# licznik.net
KiCad netlist of a schematic drawn in EAGLE
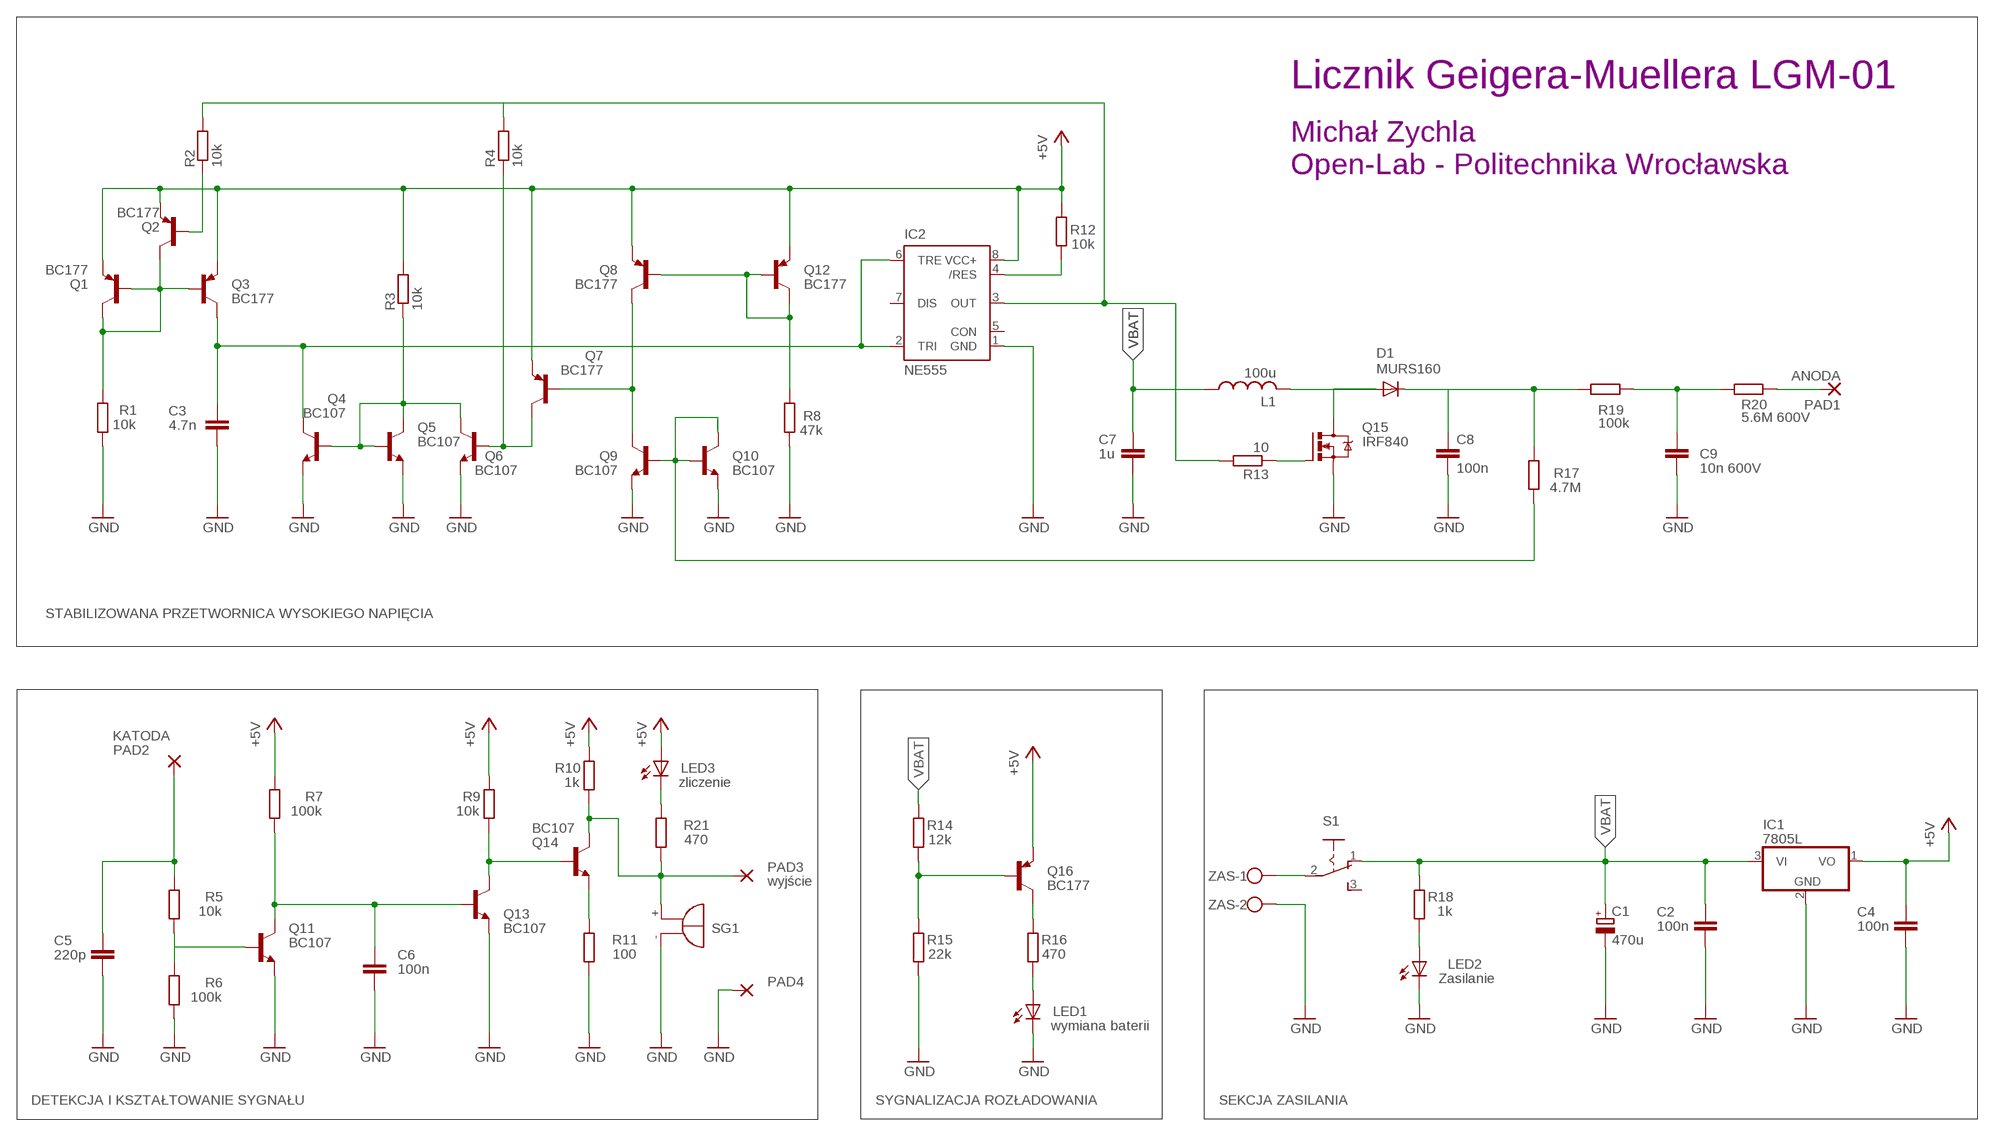
[diagram p0: schematic, sheet 1]

(export (version "E")
  (design (tool "Eeschema 10.0.6"))
  (components
    (comp (ref "C1")
      (value "470u")
      (footprint "eagle-import:E3,5-8")
      (libsource (lib "eagle-import") (part "CPOL-EUE3.5-8"))
    )
    (comp (ref "C2")
      (value "100n")
      (footprint "eagle-import:C5B3")
      (libsource (lib "eagle-import") (part "C5/3"))
    )
    (comp (ref "C3")
      (value "4.7n")
      (footprint "eagle-import:C5B3")
      (libsource (lib "eagle-import") (part "C5/3"))
    )
    (comp (ref "C4")
      (value "100n")
      (footprint "eagle-import:C5B3")
      (libsource (lib "eagle-import") (part "C5/3"))
    )
    (comp (ref "C5")
      (value "220p")
      (footprint "eagle-import:C5B3")
      (libsource (lib "eagle-import") (part "C5/3"))
    )
    (comp (ref "C6")
      (value "100n")
      (footprint "eagle-import:C5B3")
      (libsource (lib "eagle-import") (part "C5/3"))
    )
    (comp (ref "C7")
      (value "1u")
      (footprint "eagle-import:C5B3")
      (libsource (lib "eagle-import") (part "C5/3"))
    )
    (comp (ref "C8")
      (value "100n")
      (footprint "eagle-import:C075-032X103")
      (libsource (lib "eagle-import") (part "C-EU075-032X103"))
    )
    (comp (ref "C9")
      (value "10n 600V")
      (footprint "eagle-import:C5B3")
      (libsource (lib "eagle-import") (part "C5/3"))
    )
    (comp (ref "D1")
      (value "MURS160")
      (footprint "eagle-import:SMB")
      (libsource (lib "eagle-import") (part "DIODE-SMB"))
    )
    (comp (ref "IC1")
      (value "7805L")
      (footprint "eagle-import:TO92")
      (libsource (lib "eagle-import") (part "78L05"))
    )
    (comp (ref "IC2")
      (value "NE555")
      (footprint "eagle-import:DIL-08")
      (fields (field (name "MF") "Arrow Electronics") (field (name "MPN") "NE555N"))
      (libsource (lib "eagle-import") (part "NE555"))
    )
    (comp (ref "L1")
      (value "100u")
      (footprint "eagle-import:TJ3-U1")
      (libsource (lib "eagle-import") (part "L-USTJ3-U1"))
    )
    (comp (ref "LED1")
      (value "wymiana baterii")
      (footprint "eagle-import:LED3MM")
      (libsource (lib "eagle-import") (part "LED3MM"))
    )
    (comp (ref "LED2")
      (value "Zasilanie")
      (footprint "eagle-import:LED3MM")
      (libsource (lib "eagle-import") (part "LED3MM"))
    )
    (comp (ref "LED3")
      (value "zliczenie")
      (footprint "eagle-import:LED3MM")
      (libsource (lib "eagle-import") (part "LED3MM"))
    )
    (comp (ref "PAD1")
      (value "ANODA")
      (footprint "eagle-import:2,15_1,0")
      (libsource (lib "eagle-import") (part "WIREPAD2,15/1,0"))
    )
    (comp (ref "PAD2")
      (value "KATODA")
      (footprint "eagle-import:2,15_1,0")
      (libsource (lib "eagle-import") (part "WIREPAD2,15/1,0"))
    )
    (comp (ref "PAD3")
      (value "wyjście")
      (footprint "eagle-import:2,15_1,0")
      (libsource (lib "eagle-import") (part "WIREPAD2,15/1,0"))
    )
    (comp (ref "PAD4")
      (value "WIREPAD2,15/1,0")
      (footprint "eagle-import:2,15_1,0")
      (libsource (lib "eagle-import") (part "WIREPAD2,15/1,0"))
    )
    (comp (ref "Q1")
      (value "BC177")
      (footprint "eagle-import:TO18")
      (libsource (lib "eagle-import") (part "BC177"))
    )
    (comp (ref "Q2")
      (value "BC177")
      (footprint "eagle-import:TO18")
      (libsource (lib "eagle-import") (part "BC177"))
    )
    (comp (ref "Q3")
      (value "BC177")
      (footprint "eagle-import:TO18")
      (libsource (lib "eagle-import") (part "BC177"))
    )
    (comp (ref "Q4")
      (value "BC107")
      (footprint "eagle-import:TO18")
      (libsource (lib "eagle-import") (part "BC107"))
    )
    (comp (ref "Q5")
      (value "BC107")
      (footprint "eagle-import:TO18")
      (libsource (lib "eagle-import") (part "BC107"))
    )
    (comp (ref "Q6")
      (value "BC107")
      (footprint "eagle-import:TO18")
      (libsource (lib "eagle-import") (part "BC107"))
    )
    (comp (ref "Q7")
      (value "BC177")
      (footprint "eagle-import:TO18")
      (libsource (lib "eagle-import") (part "BC177"))
    )
    (comp (ref "Q8")
      (value "BC177")
      (footprint "eagle-import:TO18")
      (libsource (lib "eagle-import") (part "BC177"))
    )
    (comp (ref "Q9")
      (value "BC107")
      (footprint "eagle-import:TO18")
      (libsource (lib "eagle-import") (part "BC107"))
    )
    (comp (ref "Q10")
      (value "BC107")
      (footprint "eagle-import:TO18")
      (libsource (lib "eagle-import") (part "BC107"))
    )
    (comp (ref "Q11")
      (value "BC107")
      (footprint "eagle-import:TO18")
      (libsource (lib "eagle-import") (part "BC107"))
    )
    (comp (ref "Q12")
      (value "BC177")
      (footprint "eagle-import:TO18")
      (libsource (lib "eagle-import") (part "BC177"))
    )
    (comp (ref "Q13")
      (value "BC107")
      (footprint "eagle-import:TO18")
      (libsource (lib "eagle-import") (part "BC107"))
    )
    (comp (ref "Q14")
      (value "BC107")
      (footprint "eagle-import:TO18")
      (libsource (lib "eagle-import") (part "BC107"))
    )
    (comp (ref "Q15")
      (value "IRF840")
      (footprint "eagle-import:TO220BV")
      (libsource (lib "eagle-import") (part "IRF740"))
    )
    (comp (ref "Q16")
      (value "BC177")
      (footprint "eagle-import:TO18")
      (libsource (lib "eagle-import") (part "BC177"))
    )
    (comp (ref "R1")
      (value "10k")
      (footprint "eagle-import:0207_10")
      (libsource (lib "eagle-import") (part "R-EU_0207/10"))
    )
    (comp (ref "R2")
      (value "10k")
      (footprint "eagle-import:0207_10")
      (libsource (lib "eagle-import") (part "R-EU_0207/10"))
    )
    (comp (ref "R3")
      (value "10k")
      (footprint "eagle-import:0207_10")
      (libsource (lib "eagle-import") (part "R-EU_0207/10"))
    )
    (comp (ref "R4")
      (value "10k")
      (footprint "eagle-import:0207_10")
      (libsource (lib "eagle-import") (part "R-EU_0207/10"))
    )
    (comp (ref "R5")
      (value "10k")
      (footprint "eagle-import:0207_10")
      (libsource (lib "eagle-import") (part "R-EU_0207/10"))
    )
    (comp (ref "R6")
      (value "100k")
      (footprint "eagle-import:0207_10")
      (libsource (lib "eagle-import") (part "R-EU_0207/10"))
    )
    (comp (ref "R7")
      (value "100k")
      (footprint "eagle-import:0207_10")
      (libsource (lib "eagle-import") (part "R-EU_0207/10"))
    )
    (comp (ref "R8")
      (value "47k")
      (footprint "eagle-import:0207_10")
      (libsource (lib "eagle-import") (part "R-EU_0207/10"))
    )
    (comp (ref "R9")
      (value "10k")
      (footprint "eagle-import:0207_10")
      (libsource (lib "eagle-import") (part "R-EU_0207/10"))
    )
    (comp (ref "R10")
      (value "1k")
      (footprint "eagle-import:0207_10")
      (libsource (lib "eagle-import") (part "R-EU_0207/10"))
    )
    (comp (ref "R11")
      (value "100")
      (footprint "eagle-import:0207_10")
      (libsource (lib "eagle-import") (part "R-EU_0207/10"))
    )
    (comp (ref "R12")
      (value "10k")
      (footprint "eagle-import:0207_10")
      (libsource (lib "eagle-import") (part "R-EU_0207/10"))
    )
    (comp (ref "R13")
      (value "10")
      (footprint "eagle-import:0207_10")
      (libsource (lib "eagle-import") (part "R-EU_0207/10"))
    )
    (comp (ref "R14")
      (value "12k")
      (footprint "eagle-import:0207_10")
      (libsource (lib "eagle-import") (part "R-EU_0207/10"))
    )
    (comp (ref "R15")
      (value "22k")
      (footprint "eagle-import:0207_10")
      (libsource (lib "eagle-import") (part "R-EU_0207/10"))
    )
    (comp (ref "R16")
      (value "470")
      (footprint "eagle-import:0207_10")
      (libsource (lib "eagle-import") (part "R-EU_0207/10"))
    )
    (comp (ref "R17")
      (value "4.7M")
      (footprint "eagle-import:0207_10")
      (libsource (lib "eagle-import") (part "R-EU_0207/10"))
    )
    (comp (ref "R18")
      (value "1k")
      (footprint "eagle-import:0207_10")
      (libsource (lib "eagle-import") (part "R-EU_0207/10"))
    )
    (comp (ref "R19")
      (value "100k")
      (footprint "eagle-import:0207_10")
      (libsource (lib "eagle-import") (part "R-EU_0207/10"))
    )
    (comp (ref "R20")
      (value "5.6M 600V")
      (footprint "eagle-import:0411_12")
      (libsource (lib "eagle-import") (part "R-EU_0411/12"))
    )
    (comp (ref "R21")
      (value "470")
      (footprint "eagle-import:0207_10")
      (libsource (lib "eagle-import") (part "R-EU_0207/10"))
    )
    (comp (ref "S1")
      (value "255SB")
      (footprint "eagle-import:255SB")
      (libsource (lib "eagle-import") (part "255SB"))
    )
    (comp (ref "SG1")
      (value "F/QMBIII")
      (footprint "eagle-import:F_QMBIII")
      (libsource (lib "eagle-import") (part "F/QMBIII"))
    )
    (comp (ref "ZAS")
      (value "W237-102")
      (footprint "eagle-import:W237-102")
      (fields (field (name "MPN") "237-102"))
      (libsource (lib "eagle-import") (part "W237-102"))
    )
  )
  (nets
    (net (code "1") (name "+5V") (class "Default")
      (node (ref "C4") (pin "1") (pinfunction "1_1") (pintype "passive"))
      (node (ref "IC1") (pin "1") (pinfunction "VO_1") (pintype "passive"))
      (node (ref "IC2") (pin "8") (pinfunction "VCC+_8") (pintype "power_in"))
      (node (ref "LED3") (pin "A") (pinfunction "A_A") (pintype "passive"))
      (node (ref "Q1") (pin "1") (pinfunction "E_1") (pintype "passive"))
      (node (ref "Q12") (pin "1") (pinfunction "E_1") (pintype "passive"))
      (node (ref "Q16") (pin "1") (pinfunction "E_1") (pintype "passive"))
      (node (ref "Q2") (pin "1") (pinfunction "E_1") (pintype "passive"))
      (node (ref "Q3") (pin "1") (pinfunction "E_1") (pintype "passive"))
      (node (ref "Q7") (pin "1") (pinfunction "E_1") (pintype "passive"))
      (node (ref "Q8") (pin "1") (pinfunction "E_1") (pintype "passive"))
      (node (ref "R10") (pin "2") (pinfunction "2_2") (pintype "passive"))
      (node (ref "R12") (pin "2") (pinfunction "2_2") (pintype "passive"))
      (node (ref "R3") (pin "2") (pinfunction "2_2") (pintype "passive"))
      (node (ref "R7") (pin "2") (pinfunction "2_2") (pintype "passive"))
      (node (ref "R9") (pin "2") (pinfunction "2_2") (pintype "passive"))
    )
    (net (code "2") (name "GND") (class "Default")
      (node (ref "C1") (pin "-") (pinfunction "-_-") (pintype "passive"))
      (node (ref "C2") (pin "2") (pinfunction "2_2") (pintype "passive"))
      (node (ref "C3") (pin "2") (pinfunction "2_2") (pintype "passive"))
      (node (ref "C4") (pin "2") (pinfunction "2_2") (pintype "passive"))
      (node (ref "C5") (pin "2") (pinfunction "2_2") (pintype "passive"))
      (node (ref "C6") (pin "2") (pinfunction "2_2") (pintype "passive"))
      (node (ref "C7") (pin "2") (pinfunction "2_2") (pintype "passive"))
      (node (ref "C8") (pin "2") (pinfunction "2_2") (pintype "passive"))
      (node (ref "C9") (pin "2") (pinfunction "2_2") (pintype "passive"))
      (node (ref "IC1") (pin "2") (pinfunction "GND_2") (pintype "passive"))
      (node (ref "IC2") (pin "1") (pinfunction "GND_1") (pintype "power_in"))
      (node (ref "LED1") (pin "K") (pinfunction "C_K") (pintype "passive"))
      (node (ref "LED2") (pin "K") (pinfunction "C_K") (pintype "passive"))
      (node (ref "PAD4") (pin "1") (pinfunction "P_1") (pintype "passive"))
      (node (ref "Q10") (pin "1") (pinfunction "E_1") (pintype "passive"))
      (node (ref "Q11") (pin "1") (pinfunction "E_1") (pintype "passive"))
      (node (ref "Q13") (pin "1") (pinfunction "E_1") (pintype "passive"))
      (node (ref "Q15") (pin "S") (pinfunction "S_S") (pintype "passive"))
      (node (ref "Q4") (pin "1") (pinfunction "E_1") (pintype "passive"))
      (node (ref "Q5") (pin "1") (pinfunction "E_1") (pintype "passive"))
      (node (ref "Q6") (pin "1") (pinfunction "E_1") (pintype "passive"))
      (node (ref "Q9") (pin "1") (pinfunction "E_1") (pintype "passive"))
      (node (ref "R1") (pin "1") (pinfunction "1_1") (pintype "passive"))
      (node (ref "R11") (pin "1") (pinfunction "1_1") (pintype "passive"))
      (node (ref "R15") (pin "1") (pinfunction "1_1") (pintype "passive"))
      (node (ref "R6") (pin "1") (pinfunction "1_1") (pintype "passive"))
      (node (ref "R8") (pin "1") (pinfunction "1_1") (pintype "passive"))
      (node (ref "SG1") (pin "-") (pinfunction "+_-") (pintype "passive"))
      (node (ref "ZAS") (pin "2") (pinfunction "KL_2") (pintype "passive"))
    )
    (net (code "3") (name "Net-(C8-Pad1)") (class "Default")
      (node (ref "C8") (pin "1") (pinfunction "1_1") (pintype "passive"))
      (node (ref "D1") (pin "C") (pinfunction "C_C") (pintype "passive"))
      (node (ref "R17") (pin "2") (pinfunction "2_2") (pintype "passive"))
      (node (ref "R19") (pin "2") (pinfunction "2_2") (pintype "passive"))
    )
    (net (code "4") (name "Net-(C9-Pad1)") (class "Default")
      (node (ref "C9") (pin "1") (pinfunction "1_1") (pintype "passive"))
      (node (ref "R19") (pin "1") (pinfunction "1_1") (pintype "passive"))
      (node (ref "R20") (pin "1") (pinfunction "1_1") (pintype "passive"))
    )
    (net (code "5") (name "Net-(D1-PadA)") (class "Default")
      (node (ref "D1") (pin "A") (pinfunction "A_A") (pintype "passive"))
      (node (ref "L1") (pin "2") (pinfunction "2_2") (pintype "passive"))
      (node (ref "Q15") (pin "D") (pinfunction "D_D") (pintype "passive"))
    )
    (net (code "6") (name "Net-(IC2-OUT)") (class "Default")
      (node (ref "IC2") (pin "3") (pinfunction "OUT_3") (pintype "output"))
      (node (ref "R13") (pin "2") (pinfunction "2_2") (pintype "passive"))
      (node (ref "R2") (pin "2") (pinfunction "2_2") (pintype "passive"))
      (node (ref "R4") (pin "2") (pinfunction "2_2") (pintype "passive"))
    )
    (net (code "7") (name "Net-(IC2-TRE)") (class "Default")
      (node (ref "C3") (pin "1") (pinfunction "1_1") (pintype "passive"))
      (node (ref "IC2") (pin "2") (pinfunction "TRI_2") (pintype "input"))
      (node (ref "IC2") (pin "6") (pinfunction "TRE_6") (pintype "input"))
      (node (ref "Q3") (pin "3") (pinfunction "C_3") (pintype "passive"))
      (node (ref "Q4") (pin "3") (pinfunction "C_3") (pintype "passive"))
    )
    (net (code "8") (name "Net-(IC2-{slash}RES)") (class "Default")
      (node (ref "IC2") (pin "4") (pinfunction "/RES_4") (pintype "input"))
      (node (ref "R12") (pin "1") (pinfunction "1_1") (pintype "passive"))
    )
    (net (code "9") (name "Net-(LED1-PadA)") (class "Default")
      (node (ref "LED1") (pin "A") (pinfunction "A_A") (pintype "passive"))
      (node (ref "R16") (pin "1") (pinfunction "1_1") (pintype "passive"))
    )
    (net (code "10") (name "Net-(LED2-PadA)") (class "Default")
      (node (ref "LED2") (pin "A") (pinfunction "A_A") (pintype "passive"))
      (node (ref "R18") (pin "1") (pinfunction "1_1") (pintype "passive"))
    )
    (net (code "11") (name "Net-(LED3-C)") (class "Default")
      (node (ref "LED3") (pin "K") (pinfunction "C_K") (pintype "passive"))
      (node (ref "R21") (pin "2") (pinfunction "2_2") (pintype "passive"))
    )
    (net (code "12") (name "Net-(PAD1-P)") (class "Default")
      (node (ref "PAD1") (pin "1") (pinfunction "P_1") (pintype "passive"))
      (node (ref "R20") (pin "2") (pinfunction "2_2") (pintype "passive"))
    )
    (net (code "13") (name "Net-(PAD2-P)") (class "Default")
      (node (ref "C5") (pin "1") (pinfunction "1_1") (pintype "passive"))
      (node (ref "PAD2") (pin "1") (pinfunction "P_1") (pintype "passive"))
      (node (ref "R5") (pin "2") (pinfunction "2_2") (pintype "passive"))
    )
    (net (code "14") (name "Net-(PAD3-P)") (class "Default")
      (node (ref "PAD3") (pin "1") (pinfunction "P_1") (pintype "passive"))
      (node (ref "Q14") (pin "3") (pinfunction "C_3") (pintype "passive"))
      (node (ref "R10") (pin "1") (pinfunction "1_1") (pintype "passive"))
      (node (ref "R21") (pin "1") (pinfunction "1_1") (pintype "passive"))
      (node (ref "SG1") (pin "+") (pinfunction "-_+") (pintype "passive"))
    )
    (net (code "15") (name "Net-(Q1-B)") (class "Default")
      (node (ref "Q1") (pin "2") (pinfunction "B_2") (pintype "passive"))
      (node (ref "Q1") (pin "3") (pinfunction "C_3") (pintype "passive"))
      (node (ref "Q2") (pin "3") (pinfunction "C_3") (pintype "passive"))
      (node (ref "Q3") (pin "2") (pinfunction "B_2") (pintype "passive"))
      (node (ref "R1") (pin "2") (pinfunction "2_2") (pintype "passive"))
    )
    (net (code "16") (name "Net-(Q2-B)") (class "Default")
      (node (ref "Q2") (pin "2") (pinfunction "B_2") (pintype "passive"))
      (node (ref "R2") (pin "1") (pinfunction "1_1") (pintype "passive"))
    )
    (net (code "17") (name "Net-(Q4-B)") (class "Default")
      (node (ref "Q4") (pin "2") (pinfunction "B_2") (pintype "passive"))
      (node (ref "Q5") (pin "2") (pinfunction "B_2") (pintype "passive"))
      (node (ref "Q5") (pin "3") (pinfunction "C_3") (pintype "passive"))
      (node (ref "Q6") (pin "3") (pinfunction "C_3") (pintype "passive"))
      (node (ref "R3") (pin "1") (pinfunction "1_1") (pintype "passive"))
    )
    (net (code "18") (name "Net-(Q6-B)") (class "Default")
      (node (ref "Q6") (pin "2") (pinfunction "B_2") (pintype "passive"))
      (node (ref "Q7") (pin "3") (pinfunction "C_3") (pintype "passive"))
      (node (ref "R4") (pin "1") (pinfunction "1_1") (pintype "passive"))
    )
    (net (code "19") (name "Net-(Q7-B)") (class "Default")
      (node (ref "Q7") (pin "2") (pinfunction "B_2") (pintype "passive"))
      (node (ref "Q8") (pin "3") (pinfunction "C_3") (pintype "passive"))
      (node (ref "Q9") (pin "3") (pinfunction "C_3") (pintype "passive"))
    )
    (net (code "20") (name "Net-(Q10-B)") (class "Default")
      (node (ref "Q10") (pin "2") (pinfunction "B_2") (pintype "passive"))
      (node (ref "Q10") (pin "3") (pinfunction "C_3") (pintype "passive"))
      (node (ref "Q9") (pin "2") (pinfunction "B_2") (pintype "passive"))
      (node (ref "R17") (pin "1") (pinfunction "1_1") (pintype "passive"))
    )
    (net (code "21") (name "Net-(Q11-B)") (class "Default")
      (node (ref "Q11") (pin "2") (pinfunction "B_2") (pintype "passive"))
      (node (ref "R5") (pin "1") (pinfunction "1_1") (pintype "passive"))
      (node (ref "R6") (pin "2") (pinfunction "2_2") (pintype "passive"))
    )
    (net (code "22") (name "Net-(Q11-C)") (class "Default")
      (node (ref "C6") (pin "1") (pinfunction "1_1") (pintype "passive"))
      (node (ref "Q11") (pin "3") (pinfunction "C_3") (pintype "passive"))
      (node (ref "Q13") (pin "2") (pinfunction "B_2") (pintype "passive"))
      (node (ref "R7") (pin "1") (pinfunction "1_1") (pintype "passive"))
    )
    (net (code "23") (name "Net-(Q12-B)") (class "Default")
      (node (ref "Q12") (pin "2") (pinfunction "B_2") (pintype "passive"))
      (node (ref "Q12") (pin "3") (pinfunction "C_3") (pintype "passive"))
      (node (ref "Q8") (pin "2") (pinfunction "B_2") (pintype "passive"))
      (node (ref "R8") (pin "2") (pinfunction "2_2") (pintype "passive"))
    )
    (net (code "24") (name "Net-(Q13-C)") (class "Default")
      (node (ref "Q13") (pin "3") (pinfunction "C_3") (pintype "passive"))
      (node (ref "Q14") (pin "2") (pinfunction "B_2") (pintype "passive"))
      (node (ref "R9") (pin "1") (pinfunction "1_1") (pintype "passive"))
    )
    (net (code "25") (name "Net-(Q14-E)") (class "Default")
      (node (ref "Q14") (pin "1") (pinfunction "E_1") (pintype "passive"))
      (node (ref "R11") (pin "2") (pinfunction "2_2") (pintype "passive"))
    )
    (net (code "26") (name "Net-(Q15-PadG)") (class "Default")
      (node (ref "Q15") (pin "G") (pinfunction "G_G") (pintype "passive"))
      (node (ref "R13") (pin "1") (pinfunction "1_1") (pintype "passive"))
    )
    (net (code "27") (name "Net-(Q16-B)") (class "Default")
      (node (ref "Q16") (pin "2") (pinfunction "B_2") (pintype "passive"))
      (node (ref "R14") (pin "1") (pinfunction "1_1") (pintype "passive"))
      (node (ref "R15") (pin "2") (pinfunction "2_2") (pintype "passive"))
    )
    (net (code "28") (name "Net-(Q16-C)") (class "Default")
      (node (ref "Q16") (pin "3") (pinfunction "C_3") (pintype "passive"))
      (node (ref "R16") (pin "2") (pinfunction "2_2") (pintype "passive"))
    )
    (net (code "29") (name "Net-(S1-P)") (class "Default")
      (node (ref "S1") (pin "2") (pinfunction "P_2") (pintype "passive"))
      (node (ref "ZAS") (pin "1") (pinfunction "KL_1") (pintype "passive"))
    )
    (net (code "30") (name "VBAT") (class "Default")
      (node (ref "C1") (pin "+") (pinfunction "+_+") (pintype "passive"))
      (node (ref "C2") (pin "1") (pinfunction "1_1") (pintype "passive"))
      (node (ref "C7") (pin "1") (pinfunction "1_1") (pintype "passive"))
      (node (ref "IC1") (pin "3") (pinfunction "VI_3") (pintype "input"))
      (node (ref "L1") (pin "1") (pinfunction "1_1") (pintype "passive"))
      (node (ref "R14") (pin "2") (pinfunction "2_2") (pintype "passive"))
      (node (ref "R18") (pin "2") (pinfunction "2_2") (pintype "passive"))
      (node (ref "S1") (pin "1") (pinfunction "O_1") (pintype "passive"))
    )
    (net (code "31") (name "unconnected-(IC2-CON-Pad5)") (class "Default")
      (node (ref "IC2") (pin "5") (pinfunction "CON_5") (pintype "input"))
    )
    (net (code "32") (name "unconnected-(IC2-DIS-Pad7)") (class "Default")
      (node (ref "IC2") (pin "7") (pinfunction "DIS_7") (pintype "input"))
    )
    (net (code "33") (name "unconnected-(S1-S-Pad3)") (class "Default")
      (node (ref "S1") (pin "3") (pinfunction "S_3") (pintype "passive"))
    )
  )
)
